# FixtureMoteino-OSH.net
KiCad netlist of a schematic drawn in EAGLE
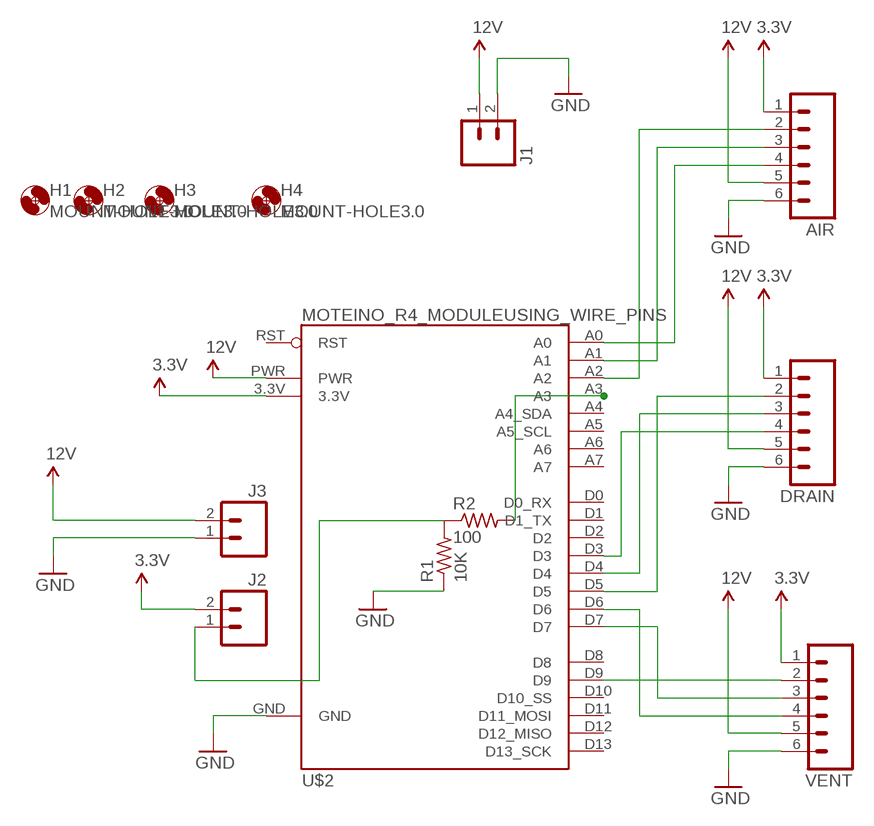
[diagram p0: schematic, sheet 1]

(export (version "E")
  (design (tool "Eeschema 10.0.6"))
  (components
    (comp (ref "AIR")
      (value "M06LOCK_LONGPADS")
      (footprint "eagle-import:1X06_LOCK_LONGPADS")
      (libsource (lib "eagle-import") (part "M06LOCK_LONGPADS"))
    )
    (comp (ref "DRAIN")
      (value "M06LOCK_LONGPADS")
      (footprint "eagle-import:1X06_LOCK_LONGPADS")
      (libsource (lib "eagle-import") (part "M06LOCK_LONGPADS"))
    )
    (comp (ref "H1")
      (value "MOUNT-HOLE3.0")
      (footprint "eagle-import:3,0")
      (libsource (lib "eagle-import") (part "MOUNT-HOLE3.0"))
    )
    (comp (ref "H2")
      (value "MOUNT-HOLE3.0")
      (footprint "eagle-import:3,0")
      (libsource (lib "eagle-import") (part "MOUNT-HOLE3.0"))
    )
    (comp (ref "H3")
      (value "MOUNT-HOLE3.0")
      (footprint "eagle-import:3,0")
      (libsource (lib "eagle-import") (part "MOUNT-HOLE3.0"))
    )
    (comp (ref "H4")
      (value "MOUNT-HOLE3.0")
      (footprint "eagle-import:3,0")
      (libsource (lib "eagle-import") (part "MOUNT-HOLE3.0"))
    )
    (comp (ref "J1")
      (value "M025MM")
      (footprint "eagle-import:SCREWTERMINAL-5MM-2")
      (libsource (lib "eagle-import") (part "M025MM"))
    )
    (comp (ref "J2")
      (value "M025MM")
      (footprint "eagle-import:SCREWTERMINAL-5MM-2")
      (libsource (lib "eagle-import") (part "M025MM"))
    )
    (comp (ref "J3")
      (value "M025MM")
      (footprint "eagle-import:SCREWTERMINAL-5MM-2")
      (libsource (lib "eagle-import") (part "M025MM"))
    )
    (comp (ref "R1")
      (value "10K")
      (footprint "eagle-import:0207_10")
      (libsource (lib "eagle-import") (part "R-US_0207/10"))
    )
    (comp (ref "R2")
      (value "100")
      (footprint "eagle-import:0207_10")
      (libsource (lib "eagle-import") (part "R-US_0207/10"))
    )
    (comp (ref "U$2")
      (value "MOTEINO_R4_MODULEUSING_WIRE_PINS")
      (footprint "eagle-import:MOTEINO_R4_WIRE")
      (libsource (lib "eagle-import") (part "MOTEINO_R4_MODULEUSING_WIRE_PINS"))
    )
    (comp (ref "VENT")
      (value "M06LOCK_LONGPADS")
      (footprint "eagle-import:1X06_LOCK_LONGPADS")
      (libsource (lib "eagle-import") (part "M06LOCK_LONGPADS"))
    )
  )
  (nets
    (net (code "1") (name "3.3V") (class "Default")
      (node (ref "AIR") (pin "1") (pinfunction "1_1") (pintype "passive"))
      (node (ref "DRAIN") (pin "1") (pinfunction "1_1") (pintype "passive"))
      (node (ref "J2") (pin "2") (pinfunction "2_2") (pintype "passive"))
      (node (ref "U$2") (pin "3.3V") (pinfunction "3.3V_3.3V") (pintype "passive"))
      (node (ref "VENT") (pin "1") (pinfunction "1_1") (pintype "passive"))
    )
    (net (code "2") (name "12V") (class "Default")
      (node (ref "AIR") (pin "5") (pinfunction "5_5") (pintype "passive"))
      (node (ref "DRAIN") (pin "5") (pinfunction "5_5") (pintype "passive"))
      (node (ref "J1") (pin "1") (pinfunction "1_1") (pintype "passive"))
      (node (ref "J3") (pin "2") (pinfunction "2_2") (pintype "passive"))
      (node (ref "U$2") (pin "PWR") (pinfunction "PWR_PWR") (pintype "passive"))
      (node (ref "VENT") (pin "5") (pinfunction "5_5") (pintype "passive"))
    )
    (net (code "3") (name "GND") (class "Default")
      (node (ref "AIR") (pin "6") (pinfunction "6_6") (pintype "passive"))
      (node (ref "DRAIN") (pin "6") (pinfunction "6_6") (pintype "passive"))
      (node (ref "J1") (pin "2") (pinfunction "2_2") (pintype "passive"))
      (node (ref "J3") (pin "1") (pinfunction "1_1") (pintype "passive"))
      (node (ref "R1") (pin "1") (pinfunction "1_1") (pintype "passive"))
      (node (ref "U$2") (pin "GND") (pinfunction "GND_GND") (pintype "power_in"))
      (node (ref "VENT") (pin "6") (pinfunction "6_6") (pintype "passive"))
    )
    (net (code "4") (name "Net-(AIR-Pad2)") (class "Default")
      (node (ref "AIR") (pin "2") (pinfunction "2_2") (pintype "passive"))
      (node (ref "U$2") (pin "A2") (pinfunction "A2_A2") (pintype "bidirectional"))
    )
    (net (code "5") (name "Net-(AIR-Pad3)") (class "Default")
      (node (ref "AIR") (pin "3") (pinfunction "3_3") (pintype "passive"))
      (node (ref "U$2") (pin "A1") (pinfunction "A1_A1") (pintype "bidirectional"))
    )
    (net (code "6") (name "Net-(AIR-Pad4)") (class "Default")
      (node (ref "AIR") (pin "4") (pinfunction "4_4") (pintype "passive"))
      (node (ref "U$2") (pin "A0") (pinfunction "A0_A0") (pintype "bidirectional"))
    )
    (net (code "7") (name "Net-(DRAIN-Pad2)") (class "Default")
      (node (ref "DRAIN") (pin "2") (pinfunction "2_2") (pintype "passive"))
      (node (ref "U$2") (pin "D5") (pinfunction "D5_D5") (pintype "bidirectional"))
    )
    (net (code "8") (name "Net-(DRAIN-Pad3)") (class "Default")
      (node (ref "DRAIN") (pin "3") (pinfunction "3_3") (pintype "passive"))
      (node (ref "U$2") (pin "D4") (pinfunction "D4_D4") (pintype "bidirectional"))
    )
    (net (code "9") (name "Net-(DRAIN-Pad4)") (class "Default")
      (node (ref "DRAIN") (pin "4") (pinfunction "4_4") (pintype "passive"))
      (node (ref "U$2") (pin "D3") (pinfunction "D3_D3") (pintype "bidirectional"))
    )
    (net (code "10") (name "Net-(J2-Pad1)") (class "Default")
      (node (ref "J2") (pin "1") (pinfunction "1_1") (pintype "passive"))
      (node (ref "R1") (pin "2") (pinfunction "2_2") (pintype "passive"))
      (node (ref "R2") (pin "1") (pinfunction "1_1") (pintype "passive"))
    )
    (net (code "11") (name "Net-(R2-Pad2)") (class "Default")
      (node (ref "R2") (pin "2") (pinfunction "2_2") (pintype "passive"))
      (node (ref "U$2") (pin "A3") (pinfunction "A3_A3") (pintype "bidirectional"))
    )
    (net (code "12") (name "Net-(U$2-PadD6)") (class "Default")
      (node (ref "U$2") (pin "D6") (pinfunction "D6_D6") (pintype "bidirectional"))
      (node (ref "VENT") (pin "4") (pinfunction "4_4") (pintype "passive"))
    )
    (net (code "13") (name "Net-(U$2-PadD7)") (class "Default")
      (node (ref "U$2") (pin "D7") (pinfunction "D7_D7") (pintype "bidirectional"))
      (node (ref "VENT") (pin "3") (pinfunction "3_3") (pintype "passive"))
    )
    (net (code "14") (name "Net-(U$2-PadD9)") (class "Default")
      (node (ref "U$2") (pin "D9") (pinfunction "D9_D9") (pintype "bidirectional"))
      (node (ref "VENT") (pin "2") (pinfunction "2_2") (pintype "passive"))
    )
    (net (code "15") (name "unconnected-(U$2-A4_SDA-PadA4)") (class "Default")
      (node (ref "U$2") (pin "A4") (pinfunction "A4_SDA_A4") (pintype "bidirectional"))
    )
    (net (code "16") (name "unconnected-(U$2-A5_SCL-PadA5)") (class "Default")
      (node (ref "U$2") (pin "A5") (pinfunction "A5_SCL_A5") (pintype "bidirectional"))
    )
    (net (code "17") (name "unconnected-(U$2-D0_RX-PadD0)") (class "Default")
      (node (ref "U$2") (pin "D0") (pinfunction "D0_RX_D0") (pintype "bidirectional"))
    )
    (net (code "18") (name "unconnected-(U$2-D1_TX-PadD1)") (class "Default")
      (node (ref "U$2") (pin "D1") (pinfunction "D1_TX_D1") (pintype "bidirectional"))
    )
    (net (code "19") (name "unconnected-(U$2-D10_SS-PadD10)") (class "Default")
      (node (ref "U$2") (pin "D10") (pinfunction "D10_SS_D10") (pintype "bidirectional"))
    )
    (net (code "20") (name "unconnected-(U$2-D11_MOSI-PadD11)") (class "Default")
      (node (ref "U$2") (pin "D11") (pinfunction "D11_MOSI_D11") (pintype "bidirectional"))
    )
    (net (code "21") (name "unconnected-(U$2-D12_MISO-PadD12)") (class "Default")
      (node (ref "U$2") (pin "D12") (pinfunction "D12_MISO_D12") (pintype "bidirectional"))
    )
    (net (code "22") (name "unconnected-(U$2-D13_SCK-PadD13)") (class "Default")
      (node (ref "U$2") (pin "D13") (pinfunction "D13_SCK_D13") (pintype "bidirectional"))
    )
    (net (code "23") (name "unconnected-(U$2-PadA6)") (class "Default")
      (node (ref "U$2") (pin "A6") (pinfunction "A6_A6") (pintype "bidirectional"))
    )
    (net (code "24") (name "unconnected-(U$2-PadA7)") (class "Default")
      (node (ref "U$2") (pin "A7") (pinfunction "A7_A7") (pintype "bidirectional"))
    )
    (net (code "25") (name "unconnected-(U$2-PadD2)") (class "Default")
      (node (ref "U$2") (pin "D2") (pinfunction "D2_D2") (pintype "bidirectional"))
    )
    (net (code "26") (name "unconnected-(U$2-PadD8)") (class "Default")
      (node (ref "U$2") (pin "D8") (pinfunction "D8_D8") (pintype "bidirectional"))
    )
    (net (code "27") (name "unconnected-(U$2-PadRST)") (class "Default")
      (node (ref "U$2") (pin "RST") (pinfunction "RST_RST") (pintype "bidirectional"))
    )
  )
)
